# V2_1.net
KiCad netlist of a schematic drawn in Altium Designer
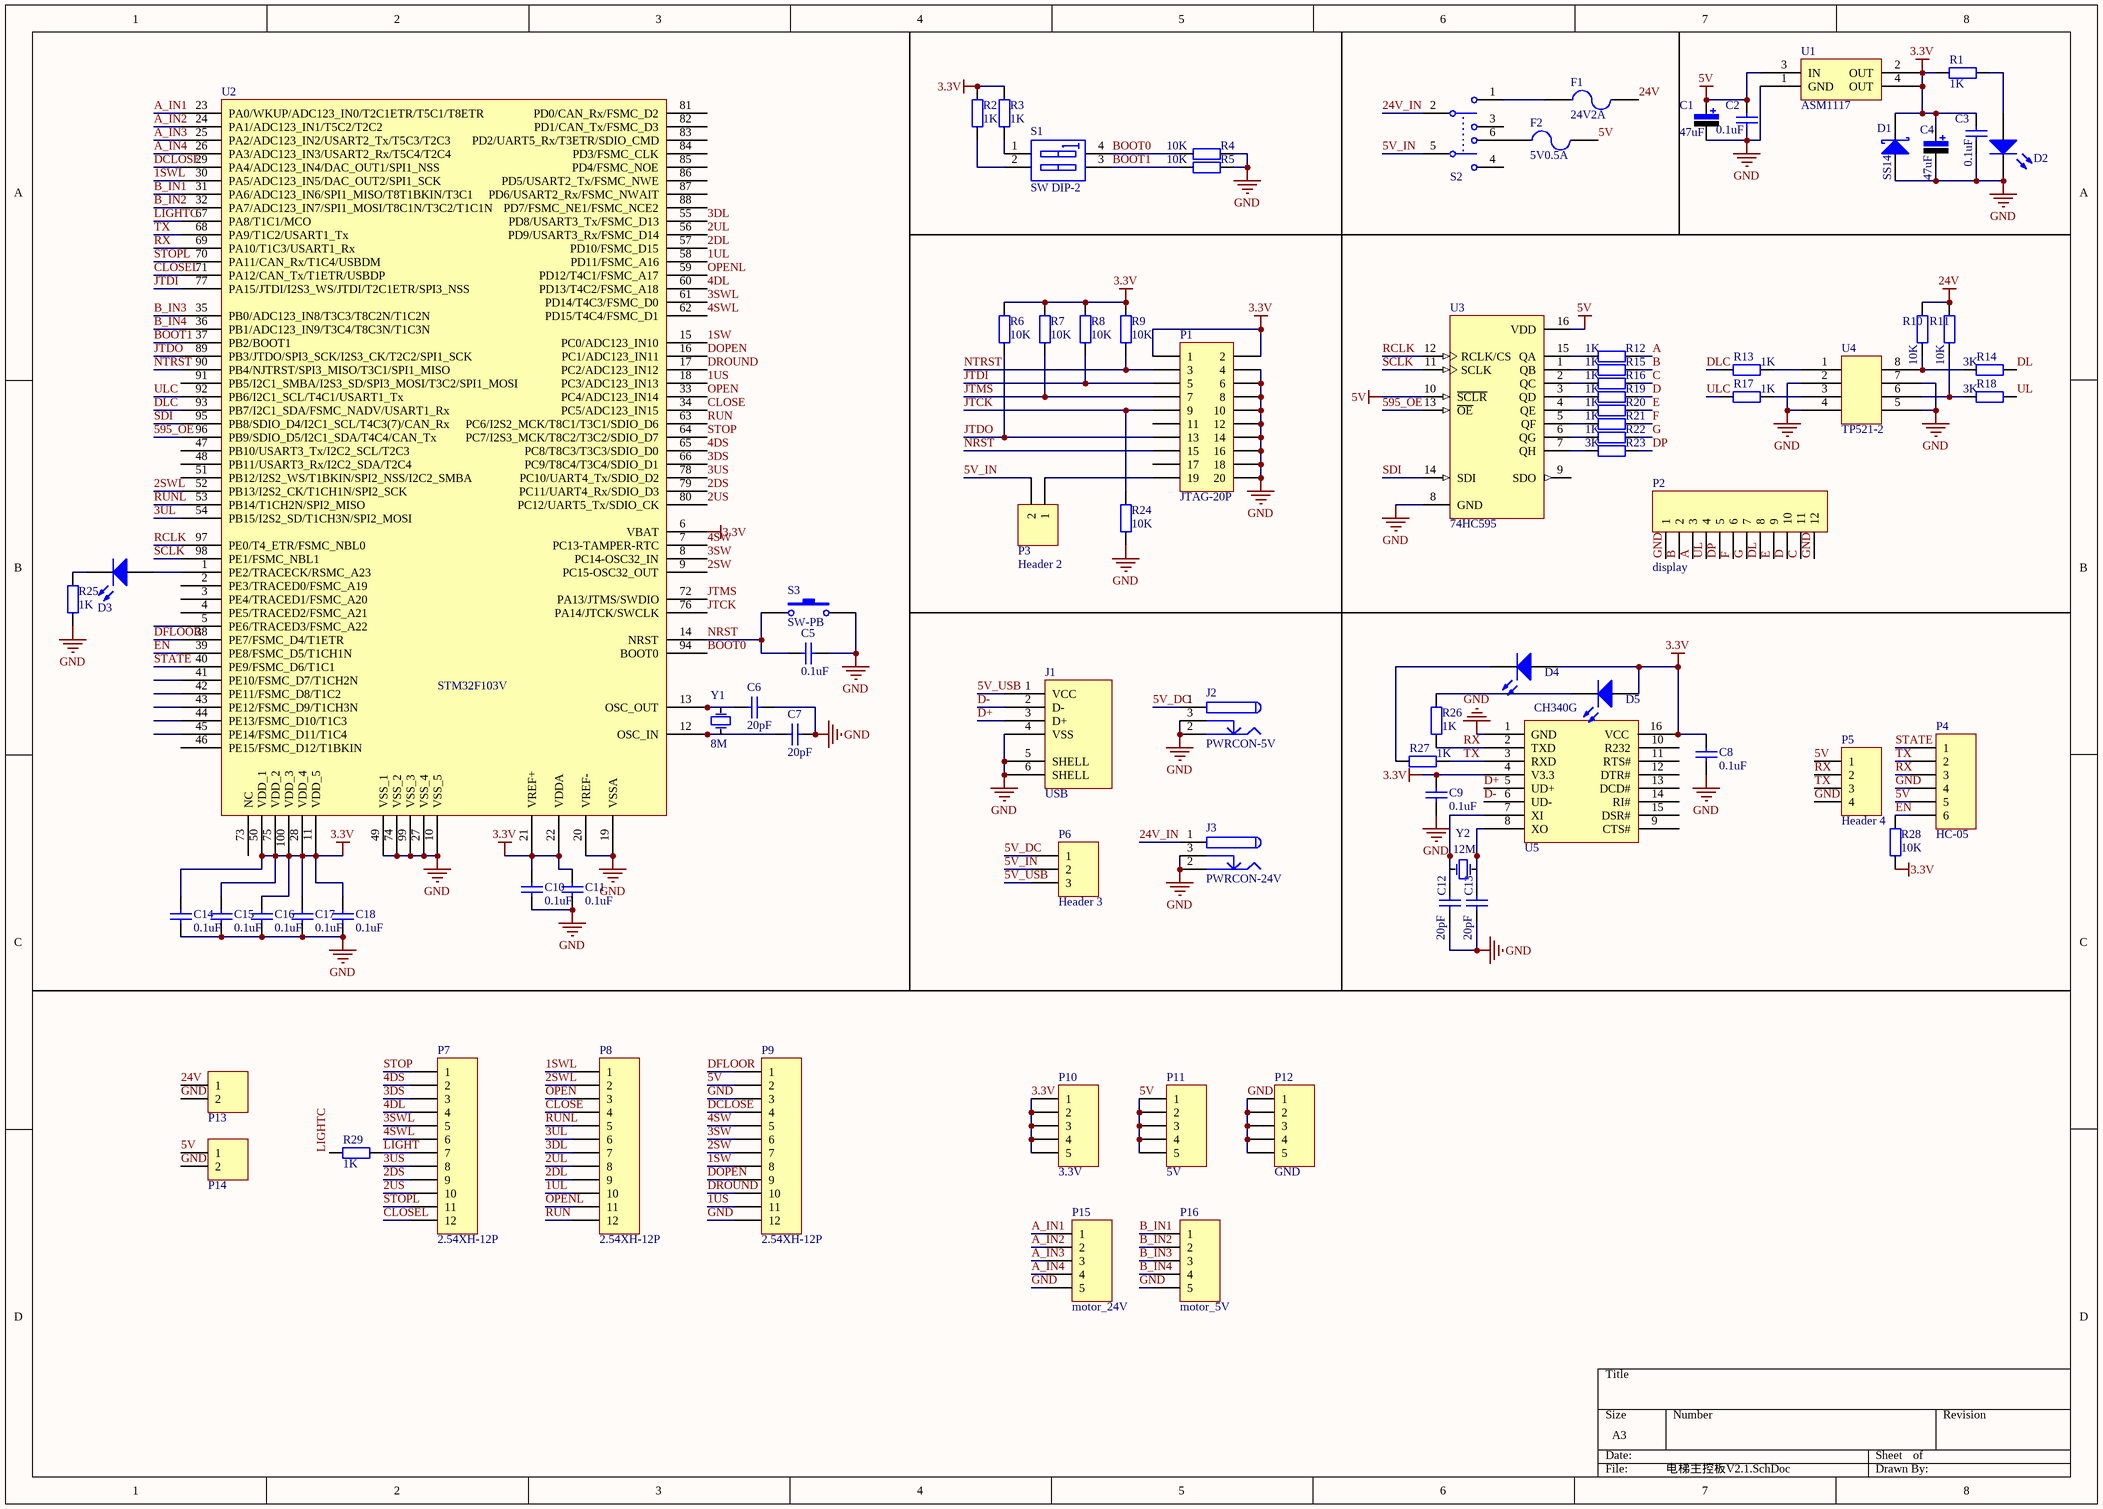
[diagram p0: 电梯主控板V2.1.SchDoc]

(export (version "E")
  (design (tool "Eeschema 10.0.6"))
  (components
    (comp (ref "C1")
      (value "47uF")
      (footprint "CAP-3528")
      (description "钽电容")
      (libsource (lib "Fszhang") (part "Cap-Pol-A"))
    )
    (comp (ref "C2")
      (value "0.1uF")
      (footprint "C-0805")
      (description "贴片瓷片电容")
      (libsource (lib "Fszhang") (part "Cap-S"))
    )
    (comp (ref "C3")
      (value "0.1uF")
      (footprint "C-0805")
      (description "贴片瓷片电容")
      (libsource (lib "Fszhang") (part "Cap-S"))
    )
    (comp (ref "C4")
      (value "47uF")
      (footprint "CAP-3528")
      (description "钽电容")
      (libsource (lib "Fszhang") (part "Cap-Pol-A"))
    )
    (comp (ref "C5")
      (value "0.1uF")
      (footprint "C-0805")
      (description "贴片瓷片电容")
      (libsource (lib "Fszhang") (part "Cap-S"))
    )
    (comp (ref "C6")
      (value "20pF")
      (footprint "C-0805")
      (description "贴片瓷片电容")
      (libsource (lib "Fszhang") (part "Cap-S"))
    )
    (comp (ref "C7")
      (value "20pF")
      (footprint "C-0805")
      (description "贴片瓷片电容")
      (libsource (lib "Fszhang") (part "Cap-S"))
    )
    (comp (ref "C8")
      (value "0.1uF")
      (footprint "C-0805")
      (description "贴片瓷片电容")
      (libsource (lib "Fszhang") (part "Cap-S"))
    )
    (comp (ref "C9")
      (value "0.1uF")
      (footprint "C-0805")
      (description "贴片瓷片电容")
      (libsource (lib "Fszhang") (part "Cap-S"))
    )
    (comp (ref "C10")
      (value "0.1uF")
      (footprint "C-0805")
      (description "贴片瓷片电容")
      (libsource (lib "Fszhang") (part "Cap-S"))
    )
    (comp (ref "C11")
      (value "0.1uF")
      (footprint "C-0805")
      (description "贴片瓷片电容")
      (libsource (lib "Fszhang") (part "Cap-S"))
    )
    (comp (ref "C12")
      (value "20pF")
      (footprint "C-0805")
      (description "贴片瓷片电容")
      (libsource (lib "Fszhang") (part "Cap-S"))
    )
    (comp (ref "C13")
      (value "20pF")
      (footprint "C-0805")
      (description "贴片瓷片电容")
      (libsource (lib "Fszhang") (part "Cap-S"))
    )
    (comp (ref "C14")
      (value "0.1uF")
      (footprint "C-0805")
      (description "贴片瓷片电容")
      (libsource (lib "Fszhang") (part "Cap-S"))
    )
    (comp (ref "C15")
      (value "0.1uF")
      (footprint "C-0805")
      (description "贴片瓷片电容")
      (libsource (lib "Fszhang") (part "Cap-S"))
    )
    (comp (ref "C16")
      (value "0.1uF")
      (footprint "C-0805")
      (description "贴片瓷片电容")
      (libsource (lib "Fszhang") (part "Cap-S"))
    )
    (comp (ref "C17")
      (value "0.1uF")
      (footprint "C-0805")
      (description "贴片瓷片电容")
      (libsource (lib "Fszhang") (part "Cap-S"))
    )
    (comp (ref "C18")
      (value "0.1uF")
      (footprint "C-0805")
      (description "贴片瓷片电容")
      (libsource (lib "Fszhang") (part "Cap-S"))
    )
    (comp (ref "D1")
      (value "Diode-Schottky")
      (footprint "D-SMA")
      (description "肖特基二极管")
      (fields (field (name "TYPE") "SS14"))
      (libsource (lib "Fszhang") (part "Diode-Schottky"))
    )
    (comp (ref "D2")
      (value "LED0")
      (footprint "LED-0805")
      (description "发光二极管")
      (libsource (lib "Fszhang") (part "LED0"))
    )
    (comp (ref "D3")
      (value "LED0")
      (footprint "LED-0805")
      (description "发光二极管")
      (libsource (lib "Fszhang") (part "LED0"))
    )
    (comp (ref "D4")
      (value "LED0")
      (footprint "LED-0805")
      (description "发光二极管")
      (libsource (lib "Fszhang") (part "LED0"))
    )
    (comp (ref "D5")
      (value "LED0")
      (footprint "LED-0805")
      (description "发光二极管")
      (libsource (lib "Fszhang") (part "LED0"))
    )
    (comp (ref "F1")
      (value "24V2A")
      (footprint "1812")
      (description "可恢复保险丝")
      (libsource (lib "Fszhang") (part "Fuse2"))
    )
    (comp (ref "F2")
      (value "5V0.5A")
      (footprint "1812")
      (description "可恢复保险丝")
      (libsource (lib "Fszhang") (part "Fuse2"))
    )
    (comp (ref "J1")
      (value "USB")
      (footprint "USB_A1")
      (description "USB接口")
      (libsource (lib "HDR_Fszhang") (part "USB"))
    )
    (comp (ref "J2")
      (value "PWRCON-5V")
      (footprint "DC-002")
      (description "直流电源端子")
      (libsource (lib "HDR_Fszhang") (part "PWRCON"))
    )
    (comp (ref "J3")
      (value "PWRCON-24V")
      (footprint "DC-005")
      (description "直流电源端子")
      (libsource (lib "HDR_Fszhang") (part "PWRCON"))
    )
    (comp (ref "P1") (value "JTAG-20P") (footprint "DC3-20P") (libsource (lib "natel") (part "JTAG-20P")))
    (comp (ref "P2") (value "display") (footprint "2.54XH-12P") (libsource (lib "natel") (part "2.54XH-12P")))
    (comp (ref "P3")
      (value "Header 2")
      (footprint "HDR1X2")
      (description "Header, 2-Pin")
      (libsource (lib "Miscellaneous Connectors") (part "Header 2"))
    )
    (comp (ref "P4")
      (value "HC-05")
      (footprint "HDR1X6")
      (description "Header, 6-Pin")
      (libsource (lib "Miscellaneous Connectors") (part "Header 6"))
    )
    (comp (ref "P5")
      (value "Header 4")
      (footprint "HDR1X4")
      (description "Header, 4-Pin")
      (libsource (lib "Miscellaneous Connectors") (part "Header 4"))
    )
    (comp (ref "P6")
      (value "Header 3")
      (footprint "HDR1X3")
      (description "Header, 3-Pin")
      (libsource (lib "Miscellaneous Connectors") (part "Header 3"))
    )
    (comp (ref "P7") (value "2.54XH-12P") (footprint "2.54XH-12P") (libsource (lib "") (part "2.54XH-12P_1")))
    (comp (ref "P8") (value "2.54XH-12P") (footprint "2.54XH-12P") (libsource (lib "") (part "2.54XH-12P_1")))
    (comp (ref "P9") (value "2.54XH-12P") (footprint "2.54XH-12P") (libsource (lib "") (part "2.54XH-12P_1")))
    (comp (ref "P10")
      (value "3.3V")
      (footprint "HDR1X5")
      (description "Header, 5-Pin")
      (libsource (lib "Miscellaneous Connectors") (part "Header 5"))
    )
    (comp (ref "P11")
      (value "5V")
      (footprint "HDR1X5")
      (description "Header, 5-Pin")
      (libsource (lib "Miscellaneous Connectors") (part "Header 5"))
    )
    (comp (ref "P12")
      (value "GND")
      (footprint "HDR1X5")
      (description "Header, 5-Pin")
      (libsource (lib "Miscellaneous Connectors") (part "Header 5"))
    )
    (comp (ref "P13") (value "KF301-2P") (footprint "KF301-2P") (libsource (lib "natel") (part "KF301-2P")))
    (comp (ref "P14") (value "KF301-2P") (footprint "KF301-2P") (libsource (lib "natel") (part "KF301-2P")))
    (comp (ref "P15")
      (value "motor_24V")
      (footprint "2.54xh-5P")
      (libsource (lib "natel") (part "2.54XH-5P"))
    )
    (comp (ref "P16") (value "motor_5V") (footprint "2.54xh-5P") (libsource (lib "natel") (part "2.54XH-5P")))
    (comp (ref "R1")
      (value "1K")
      (footprint "0805-1")
      (description "贴片电阻")
      (libsource (lib "Fszhang") (part "Res1"))
    )
    (comp (ref "R2")
      (value "1K")
      (footprint "0805-1")
      (description "贴片电阻")
      (libsource (lib "") (part "Res1_1"))
    )
    (comp (ref "R3")
      (value "1K")
      (footprint "0805-1")
      (description "贴片电阻")
      (libsource (lib "") (part "Res1_1"))
    )
    (comp (ref "R4")
      (value "10K")
      (footprint "0805-1")
      (description "贴片电阻")
      (libsource (lib "Fszhang") (part "Res1"))
    )
    (comp (ref "R5")
      (value "10K")
      (footprint "0805-1")
      (description "贴片电阻")
      (libsource (lib "Fszhang") (part "Res1"))
    )
    (comp (ref "R6")
      (value "10K")
      (footprint "0805-1")
      (description "贴片电阻")
      (libsource (lib "") (part "Res1_1"))
    )
    (comp (ref "R7")
      (value "10K")
      (footprint "0805-1")
      (description "贴片电阻")
      (libsource (lib "") (part "Res1_1"))
    )
    (comp (ref "R8")
      (value "10K")
      (footprint "0805-1")
      (description "贴片电阻")
      (libsource (lib "") (part "Res1_1"))
    )
    (comp (ref "R9")
      (value "10K")
      (footprint "0805-1")
      (description "贴片电阻")
      (libsource (lib "") (part "Res1_1"))
    )
    (comp (ref "R10")
      (value "10K")
      (footprint "0805-1")
      (description "贴片电阻")
      (libsource (lib "") (part "Res1_1"))
    )
    (comp (ref "R11")
      (value "10K")
      (footprint "0805-1")
      (description "贴片电阻")
      (libsource (lib "") (part "Res1_1"))
    )
    (comp (ref "R12")
      (value "1K")
      (footprint "0805-1")
      (description "贴片电阻")
      (libsource (lib "Fszhang") (part "Res1"))
    )
    (comp (ref "R13")
      (value "1K")
      (footprint "0805-1")
      (description "贴片电阻")
      (libsource (lib "Fszhang") (part "Res1"))
    )
    (comp (ref "R14")
      (value "3K")
      (footprint "0805-1")
      (description "贴片电阻")
      (libsource (lib "Fszhang") (part "Res1"))
    )
    (comp (ref "R15")
      (value "1K")
      (footprint "0805-1")
      (description "贴片电阻")
      (libsource (lib "Fszhang") (part "Res1"))
    )
    (comp (ref "R16")
      (value "1K")
      (footprint "0805-1")
      (description "贴片电阻")
      (libsource (lib "Fszhang") (part "Res1"))
    )
    (comp (ref "R17")
      (value "1K")
      (footprint "0805-1")
      (description "贴片电阻")
      (libsource (lib "Fszhang") (part "Res1"))
    )
    (comp (ref "R18")
      (value "3K")
      (footprint "0805-1")
      (description "贴片电阻")
      (libsource (lib "Fszhang") (part "Res1"))
    )
    (comp (ref "R19")
      (value "1K")
      (footprint "0805-1")
      (description "贴片电阻")
      (libsource (lib "Fszhang") (part "Res1"))
    )
    (comp (ref "R20")
      (value "1K")
      (footprint "0805-1")
      (description "贴片电阻")
      (libsource (lib "Fszhang") (part "Res1"))
    )
    (comp (ref "R21")
      (value "1K")
      (footprint "0805-1")
      (description "贴片电阻")
      (libsource (lib "Fszhang") (part "Res1"))
    )
    (comp (ref "R22")
      (value "1K")
      (footprint "0805-1")
      (description "贴片电阻")
      (libsource (lib "Fszhang") (part "Res1"))
    )
    (comp (ref "R23")
      (value "3K")
      (footprint "0805-1")
      (description "贴片电阻")
      (libsource (lib "Fszhang") (part "Res1"))
    )
    (comp (ref "R24")
      (value "10K")
      (footprint "0805-1")
      (description "贴片电阻")
      (libsource (lib "") (part "Res1_1"))
    )
    (comp (ref "R25")
      (value "1K")
      (footprint "0805-1")
      (description "贴片电阻")
      (libsource (lib "") (part "Res1_1"))
    )
    (comp (ref "R26")
      (value "1K")
      (footprint "0805-1")
      (description "贴片电阻")
      (libsource (lib "") (part "Res1_1"))
    )
    (comp (ref "R27")
      (value "1K")
      (footprint "0805-1")
      (description "贴片电阻")
      (libsource (lib "Fszhang") (part "Res1"))
    )
    (comp (ref "R28")
      (value "10K")
      (footprint "0805-1")
      (description "贴片电阻")
      (libsource (lib "") (part "Res1_1"))
    )
    (comp (ref "R29")
      (value "1K")
      (footprint "0805-1")
      (description "贴片电阻")
      (libsource (lib "Fszhang") (part "Res1"))
    )
    (comp (ref "S1")
      (value "SW DIP-2")
      (footprint "DIP-4")
      (description "DIP Switch, 2 Position, SPST")
      (libsource (lib "Miscellaneous Devices") (part "SW DIP-2"))
    )
    (comp (ref "S2") (value "六脚钮子开关") (footprint "六脚纽子开关") (libsource (lib "natel") (part "六脚钮子开关")))
    (comp (ref "S3")
      (value "SW-PB")
      (footprint "SW_PB2_A1")
      (description "微动开关")
      (libsource (lib "Fszhang") (part "SW-PB"))
    )
    (comp (ref "U1")
      (value "ASM1117")
      (footprint "SOT223")
      (description "3.3V稳压芯片")
      (libsource (lib "Fszhang") (part "ASM1117"))
    )
    (comp (ref "U2")
      (value "STM32F103V")
      (footprint "LQFP-100")
      (description "STM32单片机100引脚")
      (libsource (lib "Fszhang") (part "STM32F103V"))
    )
    (comp (ref "U3")
      (value "74HC595")
      (footprint "SOIC-16")
      (description "移位寄存器")
      (libsource (lib "Fszhang") (part "74HC595"))
    )
    (comp (ref "U4") (value "TP521-2") (footprint "DIP8") (libsource (lib "natel") (part "P521-2")))
    (comp (ref "U5") (value "CH340G") (footprint "SOP16") (libsource (lib "natel") (part "CH340G")))
    (comp (ref "Y1")
      (value "8M")
      (footprint "X-HC-49S")
      (description "晶振")
      (libsource (lib "Fszhang") (part "XTAL"))
    )
    (comp (ref "Y2")
      (value "12M")
      (footprint "X-HC-49S")
      (description "晶振")
      (libsource (lib "Fszhang") (part "XTAL"))
    )
  )
  (nets
    (net (code "1") (name "/1SW") (class "Default")
      (node (ref "P9") (pin "8") (pinfunction "8_8") (pintype "passive"))
      (node (ref "U2") (pin "15") (pinfunction "PC0/ADC123_IN10_15") (pintype "passive"))
    )
    (net (code "2") (name "/1SWL") (class "Default")
      (node (ref "P8") (pin "1") (pinfunction "1_1") (pintype "passive"))
      (node (ref "U2") (pin "30") (pinfunction "PA5/ADC123_IN5/DAC_OUT2/SPI1_SCK_30") (pintype "passive"))
    )
    (net (code "3") (name "/1UL") (class "Default")
      (node (ref "P8") (pin "10") (pinfunction "10_10") (pintype "passive"))
      (node (ref "U2") (pin "58") (pinfunction "PD11/FSMC_A16_58") (pintype "passive"))
    )
    (net (code "4") (name "/1US") (class "Default")
      (node (ref "P9") (pin "11") (pinfunction "11_11") (pintype "passive"))
      (node (ref "U2") (pin "18") (pinfunction "PC3/ADC123_IN13_18") (pintype "passive"))
    )
    (net (code "5") (name "/2DL") (class "Default")
      (node (ref "P8") (pin "9") (pinfunction "9_9") (pintype "passive"))
      (node (ref "U2") (pin "57") (pinfunction "PD10/FSMC_D15_57") (pintype "passive"))
    )
    (net (code "6") (name "/2DS") (class "Default")
      (node (ref "P7") (pin "9") (pinfunction "9_9") (pintype "passive"))
      (node (ref "U2") (pin "79") (pinfunction "PC11/UART4_Rx/SDIO_D3_79") (pintype "passive"))
    )
    (net (code "7") (name "/2SW") (class "Default")
      (node (ref "P9") (pin "7") (pinfunction "7_7") (pintype "passive"))
      (node (ref "U2") (pin "9") (pinfunction "PC15-OSC32_OUT_9") (pintype "passive"))
    )
    (net (code "8") (name "/2SWL") (class "Default")
      (node (ref "P8") (pin "2") (pinfunction "2_2") (pintype "passive"))
      (node (ref "U2") (pin "52") (pinfunction "PB13/I2S2_CK/T1CH1N/SPI2_SCK_52") (pintype "passive"))
    )
    (net (code "9") (name "/2UL") (class "Default")
      (node (ref "P8") (pin "8") (pinfunction "8_8") (pintype "passive"))
      (node (ref "U2") (pin "56") (pinfunction "PD9/USART3_Rx/FSMC_D14_56") (pintype "passive"))
    )
    (net (code "10") (name "/2US") (class "Default")
      (node (ref "P7") (pin "10") (pinfunction "10_10") (pintype "passive"))
      (node (ref "U2") (pin "80") (pinfunction "PC12/UART5_Tx/SDIO_CK_80") (pintype "passive"))
    )
    (net (code "11") (name "/3DL") (class "Default")
      (node (ref "P8") (pin "7") (pinfunction "7_7") (pintype "passive"))
      (node (ref "U2") (pin "55") (pinfunction "PD8/USART3_Tx/FSMC_D13_55") (pintype "passive"))
    )
    (net (code "12") (name "/3DS") (class "Default")
      (node (ref "P7") (pin "3") (pinfunction "3_3") (pintype "passive"))
      (node (ref "U2") (pin "66") (pinfunction "PC9/T8C4/T3C4/SDIO_D1_66") (pintype "passive"))
    )
    (net (code "13") (name "/3SW") (class "Default")
      (node (ref "P9") (pin "6") (pinfunction "6_6") (pintype "passive"))
      (node (ref "U2") (pin "8") (pinfunction "PC14-OSC32_IN_8") (pintype "passive"))
    )
    (net (code "14") (name "/3SWL") (class "Default")
      (node (ref "P7") (pin "5") (pinfunction "5_5") (pintype "passive"))
      (node (ref "U2") (pin "61") (pinfunction "PD14/T4C3/FSMC_D0_61") (pintype "passive"))
    )
    (net (code "15") (name "/3UL") (class "Default")
      (node (ref "P8") (pin "6") (pinfunction "6_6") (pintype "passive"))
      (node (ref "U2") (pin "54") (pinfunction "PB15/I2S2_SD/T1CH3N/SPI2_MOSI_54") (pintype "passive"))
    )
    (net (code "16") (name "/3US") (class "Default")
      (node (ref "P7") (pin "8") (pinfunction "8_8") (pintype "passive"))
      (node (ref "U2") (pin "78") (pinfunction "PC10/UART4_Tx/SDIO_D2_78") (pintype "passive"))
    )
    (net (code "17") (name "/4DL") (class "Default")
      (node (ref "P7") (pin "4") (pinfunction "4_4") (pintype "passive"))
      (node (ref "U2") (pin "60") (pinfunction "PD13/T4C2/FSMC_A18_60") (pintype "passive"))
    )
    (net (code "18") (name "/4DS") (class "Default")
      (node (ref "P7") (pin "2") (pinfunction "2_2") (pintype "passive"))
      (node (ref "U2") (pin "65") (pinfunction "PC8/T8C3/T3C3/SDIO_D0_65") (pintype "passive"))
    )
    (net (code "19") (name "/4SW") (class "Default")
      (node (ref "P9") (pin "5") (pinfunction "5_5") (pintype "passive"))
      (node (ref "U2") (pin "7") (pinfunction "PC13-TAMPER-RTC_7") (pintype "passive"))
    )
    (net (code "20") (name "/4SWL") (class "Default")
      (node (ref "P7") (pin "6") (pinfunction "6_6") (pintype "passive"))
      (node (ref "U2") (pin "62") (pinfunction "PD15/T4C4/FSMC_D1_62") (pintype "passive"))
    )
    (net (code "21") (name "/5V_DC") (class "Default")
      (node (ref "J2") (pin "1") (pinfunction "1_1") (pintype "power_in"))
      (node (ref "P6") (pin "1") (pinfunction "1_1") (pintype "passive"))
    )
    (net (code "22") (name "/5V_IN") (class "Default")
      (node (ref "P3") (pin "2") (pinfunction "2_2") (pintype "passive"))
      (node (ref "P6") (pin "2") (pinfunction "2_2") (pintype "passive"))
      (node (ref "S2") (pin "5") (pinfunction "5_5") (pintype "passive"))
    )
    (net (code "23") (name "/5V_USB") (class "Default")
      (node (ref "J1") (pin "1") (pinfunction "VCC_1") (pintype "passive"))
      (node (ref "P6") (pin "3") (pinfunction "3_3") (pintype "passive"))
    )
    (net (code "24") (name "/24V_IN") (class "Default")
      (node (ref "J3") (pin "1") (pinfunction "1_1") (pintype "power_in"))
      (node (ref "S2") (pin "2") (pinfunction "2_2") (pintype "passive"))
    )
    (net (code "25") (name "/595_OE") (class "Default")
      (node (ref "U2") (pin "96") (pinfunction "PB9/SDIO_D5/I2C1_SDA/T4C4/CAN_Tx_96") (pintype "passive"))
      (node (ref "U3") (pin "13") (pinfunction "~{OE}_13") (pintype "input"))
    )
    (net (code "26") (name "/A") (class "Default")
      (node (ref "P2") (pin "3") (pinfunction "3_3") (pintype "passive"))
      (node (ref "R12") (pin "2") (pinfunction "2_2") (pintype "passive"))
    )
    (net (code "27") (name "/A_IN1") (class "Default")
      (node (ref "P15") (pin "1") (pinfunction "1_1") (pintype "passive"))
      (node (ref "U2") (pin "23") (pinfunction "PA0/WKUP/ADC123_IN0/T2C1ETR/T5C1/T8ETR_23") (pintype "passive"))
    )
    (net (code "28") (name "/A_IN2") (class "Default")
      (node (ref "P15") (pin "2") (pinfunction "2_2") (pintype "passive"))
      (node (ref "U2") (pin "24") (pinfunction "PA1/ADC123_IN1/T5C2/T2C2_24") (pintype "passive"))
    )
    (net (code "29") (name "/A_IN3") (class "Default")
      (node (ref "P15") (pin "3") (pinfunction "3_3") (pintype "passive"))
      (node (ref "U2") (pin "25") (pinfunction "PA2/ADC123_IN2/USART2_Tx/T5C3/T2C3_25") (pintype "passive"))
    )
    (net (code "30") (name "/A_IN4") (class "Default")
      (node (ref "P15") (pin "4") (pinfunction "4_4") (pintype "passive"))
      (node (ref "U2") (pin "26") (pinfunction "PA3/ADC123_IN3/USART2_Rx/T5C4/T2C4_26") (pintype "passive"))
    )
    (net (code "31") (name "/B") (class "Default")
      (node (ref "P2") (pin "2") (pinfunction "2_2") (pintype "passive"))
      (node (ref "R15") (pin "2") (pinfunction "2_2") (pintype "passive"))
    )
    (net (code "32") (name "/BOOT0") (class "Default")
      (node (ref "R4") (pin "1") (pinfunction "1_1") (pintype "passive"))
      (node (ref "S1") (pin "4") (pinfunction "B1_4") (pintype "passive"))
      (node (ref "U2") (pin "94") (pinfunction "BOOT0_94") (pintype "passive"))
    )
    (net (code "33") (name "/BOOT1") (class "Default")
      (node (ref "R5") (pin "1") (pinfunction "1_1") (pintype "passive"))
      (node (ref "S1") (pin "3") (pinfunction "B2_3") (pintype "passive"))
      (node (ref "U2") (pin "37") (pinfunction "PB2/BOOT1_37") (pintype "passive"))
    )
    (net (code "34") (name "/B_IN1") (class "Default")
      (node (ref "P16") (pin "1") (pinfunction "1_1") (pintype "passive"))
      (node (ref "U2") (pin "31") (pinfunction "PA6/ADC123_IN6/SPI1_MISO/T8T1BKIN/T3C1_31") (pintype "passive"))
    )
    (net (code "35") (name "/B_IN2") (class "Default")
      (node (ref "P16") (pin "2") (pinfunction "2_2") (pintype "passive"))
      (node (ref "U2") (pin "32") (pinfunction "PA7/ADC123_IN7/SPI1_MOSI/T8C1N/T3C2/T1C1N_32") (pintype "passive"))
    )
    (net (code "36") (name "/B_IN3") (class "Default")
      (node (ref "P16") (pin "3") (pinfunction "3_3") (pintype "passive"))
      (node (ref "U2") (pin "35") (pinfunction "PB0/ADC123_IN8/T3C3/T8C2N/T1C2N_35") (pintype "passive"))
    )
    (net (code "37") (name "/B_IN4") (class "Default")
      (node (ref "P16") (pin "4") (pinfunction "4_4") (pintype "passive"))
      (node (ref "U2") (pin "36") (pinfunction "PB1/ADC123_IN9/T3C4/T8C3N/T1C3N_36") (pintype "passive"))
    )
    (net (code "38") (name "/C") (class "Default")
      (node (ref "P2") (pin "11") (pinfunction "11_11") (pintype "passive"))
      (node (ref "R16") (pin "2") (pinfunction "2_2") (pintype "passive"))
    )
    (net (code "39") (name "/CLOSE") (class "Default")
      (node (ref "P8") (pin "4") (pinfunction "4_4") (pintype "passive"))
      (node (ref "U2") (pin "34") (pinfunction "PC5/ADC123_IN15_34") (pintype "passive"))
    )
    (net (code "40") (name "/CLOSEL") (class "Default")
      (node (ref "P7") (pin "12") (pinfunction "12_12") (pintype "passive"))
      (node (ref "U2") (pin "71") (pinfunction "PA12/CAN_Tx/T1ETR/USBDP_71") (pintype "passive"))
    )
    (net (code "41") (name "/D") (class "Default")
      (node (ref "P2") (pin "10") (pinfunction "10_10") (pintype "passive"))
      (node (ref "R19") (pin "2") (pinfunction "2_2") (pintype "passive"))
    )
    (net (code "42") (name "/D+") (class "Default")
      (node (ref "J1") (pin "3") (pinfunction "D+_3") (pintype "passive"))
      (node (ref "U5") (pin "5") (pinfunction "UD+_5") (pintype "passive"))
    )
    (net (code "43") (name "/D-") (class "Default")
      (node (ref "J1") (pin "2") (pinfunction "D-_2") (pintype "passive"))
      (node (ref "U5") (pin "6") (pinfunction "UD-_6") (pintype "passive"))
    )
    (net (code "44") (name "/DCLOSE") (class "Default")
      (node (ref "P9") (pin "4") (pinfunction "4_4") (pintype "passive"))
      (node (ref "U2") (pin "29") (pinfunction "PA4/ADC123_IN4/DAC_OUT1/SPI1_NSS_29") (pintype "passive"))
    )
    (net (code "45") (name "/DFLOOR") (class "Default")
      (node (ref "P9") (pin "1") (pinfunction "1_1") (pintype "passive"))
      (node (ref "U2") (pin "38") (pinfunction "PE7/FSMC_D4/T1ETR_38") (pintype "passive"))
    )
    (net (code "46") (name "/DL") (class "Default")
      (node (ref "P2") (pin "8") (pinfunction "8_8") (pintype "passive"))
      (node (ref "R14") (pin "2") (pinfunction "2_2") (pintype "passive"))
    )
    (net (code "47") (name "/DLC") (class "Default")
      (node (ref "R13") (pin "1") (pinfunction "1_1") (pintype "passive"))
      (node (ref "U2") (pin "93") (pinfunction "PB7/I2C1_SDA/FSMC_NADV/USART1_Rx_93") (pintype "passive"))
    )
    (net (code "48") (name "/DOPEN") (class "Default")
      (node (ref "P9") (pin "9") (pinfunction "9_9") (pintype "passive"))
      (node (ref "U2") (pin "16") (pinfunction "PC1/ADC123_IN11_16") (pintype "passive"))
    )
    (net (code "49") (name "/DP") (class "Default")
      (node (ref "P2") (pin "5") (pinfunction "5_5") (pintype "passive"))
      (node (ref "R23") (pin "2") (pinfunction "2_2") (pintype "passive"))
    )
    (net (code "50") (name "/DROUND") (class "Default")
      (node (ref "P9") (pin "10") (pinfunction "10_10") (pintype "passive"))
      (node (ref "U2") (pin "17") (pinfunction "PC2/ADC123_IN12_17") (pintype "passive"))
    )
    (net (code "51") (name "/E") (class "Default")
      (node (ref "P2") (pin "9") (pinfunction "9_9") (pintype "passive"))
      (node (ref "R20") (pin "2") (pinfunction "2_2") (pintype "passive"))
    )
    (net (code "52") (name "/EN") (class "Default")
      (node (ref "P4") (pin "6") (pinfunction "6_6") (pintype "passive"))
      (node (ref "R28") (pin "2") (pinfunction "2_2") (pintype "passive"))
      (node (ref "U2") (pin "39") (pinfunction "PE8/FSMC_D5/T1CH1N_39") (pintype "passive"))
    )
    (net (code "53") (name "/F") (class "Default")
      (node (ref "P2") (pin "6") (pinfunction "6_6") (pintype "passive"))
      (node (ref "R21") (pin "2") (pinfunction "2_2") (pintype "passive"))
    )
    (net (code "54") (name "/G") (class "Default")
      (node (ref "P2") (pin "7") (pinfunction "7_7") (pintype "passive"))
      (node (ref "R22") (pin "2") (pinfunction "2_2") (pintype "passive"))
    )
    (net (code "55") (name "/JTCK") (class "Default")
      (node (ref "P1") (pin "9") (pinfunction "9_9") (pintype "passive"))
      (node (ref "R24") (pin "2") (pinfunction "2_2") (pintype "passive"))
      (node (ref "U2") (pin "76") (pinfunction "PA14/JTCK/SWCLK_76") (pintype "passive"))
    )
    (net (code "56") (name "/JTDI") (class "Default")
      (node (ref "P1") (pin "5") (pinfunction "5_5") (pintype "passive"))
      (node (ref "R8") (pin "1") (pinfunction "1_1") (pintype "passive"))
      (node (ref "U2") (pin "77") (pinfunction "PA15/JTDI/I2S3_WS/JTDI/T2C1ETR/SPI3_NSS_77") (pintype "passive"))
    )
    (net (code "57") (name "/JTDO") (class "Default")
      (node (ref "P1") (pin "13") (pinfunction "13_13") (pintype "passive"))
      (node (ref "R6") (pin "1") (pinfunction "1_1") (pintype "passive"))
      (node (ref "U2") (pin "89") (pinfunction "PB3/JTDO/SPI3_SCK/I2S3_CK/T2C2/SPI1_SCK_89") (pintype "passive"))
    )
    (net (code "58") (name "/JTMS") (class "Default")
      (node (ref "P1") (pin "7") (pinfunction "7_7") (pintype "passive"))
      (node (ref "R7") (pin "1") (pinfunction "1_1") (pintype "passive"))
      (node (ref "U2") (pin "72") (pinfunction "PA13/JTMS/SWDIO_72") (pintype "passive"))
    )
    (net (code "59") (name "/LIGHT") (class "Default")
      (node (ref "P7") (pin "7") (pinfunction "7_7") (pintype "passive"))
      (node (ref "R29") (pin "2") (pinfunction "2_2") (pintype "passive"))
    )
    (net (code "60") (name "/LIGHTC") (class "Default")
      (node (ref "R29") (pin "1") (pinfunction "1_1") (pintype "passive"))
      (node (ref "U2") (pin "67") (pinfunction "PA8/T1C1/MCO_67") (pintype "passive"))
    )
    (net (code "61") (name "/NRST") (class "Default")
      (node (ref "C5") (pin "1") (pinfunction "1_1") (pintype "passive"))
      (node (ref "P1") (pin "15") (pinfunction "15_15") (pintype "passive"))
      (node (ref "S3") (pin "1") (pinfunction "1_1") (pintype "passive"))
      (node (ref "U2") (pin "14") (pinfunction "NRST_14") (pintype "passive"))
    )
    (net (code "62") (name "/NTRST") (class "Default")
      (node (ref "P1") (pin "3") (pinfunction "3_3") (pintype "passive"))
      (node (ref "R9") (pin "1") (pinfunction "1_1") (pintype "passive"))
      (node (ref "U2") (pin "90") (pinfunction "PB4/NJTRST/SPI3_MISO/T3C1/SPI1_MISO_90") (pintype "passive"))
    )
    (net (code "63") (name "/OPEN") (class "Default")
      (node (ref "P8") (pin "3") (pinfunction "3_3") (pintype "passive"))
      (node (ref "U2") (pin "33") (pinfunction "PC4/ADC123_IN14_33") (pintype "passive"))
    )
    (net (code "64") (name "/OPENL") (class "Default")
      (node (ref "P8") (pin "11") (pinfunction "11_11") (pintype "passive"))
      (node (ref "U2") (pin "59") (pinfunction "PD12/T4C1/FSMC_A17_59") (pintype "passive"))
    )
    (net (code "65") (name "/RCLK") (class "Default")
      (node (ref "U2") (pin "97") (pinfunction "PE0/T4_ETR/FSMC_NBL0_97") (pintype "passive"))
      (node (ref "U3") (pin "12") (pinfunction "RCLK/CS_12") (pintype "input"))
    )
    (net (code "66") (name "/RUN") (class "Default")
      (node (ref "P8") (pin "12") (pinfunction "12_12") (pintype "passive"))
      (node (ref "U2") (pin "63") (pinfunction "PC6/I2S2_MCK/T8C1/T3C1/SDIO_D6_63") (pintype "passive"))
    )
    (net (code "67") (name "/RUNL") (class "Default")
      (node (ref "P8") (pin "5") (pinfunction "5_5") (pintype "passive"))
      (node (ref "U2") (pin "53") (pinfunction "PB14/T1CH2N/SPI2_MISO_53") (pintype "passive"))
    )
    (net (code "68") (name "/RX") (class "Default")
      (node (ref "P4") (pin "3") (pinfunction "3_3") (pintype "passive"))
      (node (ref "P5") (pin "2") (pinfunction "2_2") (pintype "passive"))
      (node (ref "R26") (pin "1") (pinfunction "1_1") (pintype "passive"))
      (node (ref "U2") (pin "69") (pinfunction "PA10/T1C3/USART1_Rx_69") (pintype "passive"))
      (node (ref "U5") (pin "2") (pinfunction "TXD_2") (pintype "passive"))
    )
    (net (code "69") (name "/SCLK") (class "Default")
      (node (ref "U2") (pin "98") (pinfunction "PE1/FSMC_NBL1_98") (pintype "passive"))
      (node (ref "U3") (pin "11") (pinfunction "SCLK_11") (pintype "input"))
    )
    (net (code "70") (name "/SDI") (class "Default")
      (node (ref "U2") (pin "95") (pinfunction "PB8/SDIO_D4/I2C1_SCL/T4C3(7)/CAN_Rx_95") (pintype "passive"))
      (node (ref "U3") (pin "14") (pinfunction "SDI_14") (pintype "input"))
    )
    (net (code "71") (name "/STATE") (class "Default")
      (node (ref "P4") (pin "1") (pinfunction "1_1") (pintype "passive"))
      (node (ref "U2") (pin "40") (pinfunction "PE9/FSMC_D6/T1C1_40") (pintype "passive"))
    )
    (net (code "72") (name "/STOP") (class "Default")
      (node (ref "P7") (pin "1") (pinfunction "1_1") (pintype "passive"))
      (node (ref "U2") (pin "64") (pinfunction "PC7/I2S3_MCK/T8C2/T3C2/SDIO_D7_64") (pintype "passive"))
    )
    (net (code "73") (name "/STOPL") (class "Default")
      (node (ref "P7") (pin "11") (pinfunction "11_11") (pintype "passive"))
      (node (ref "U2") (pin "70") (pinfunction "PA11/CAN_Rx/T1C4/USBDM_70") (pintype "passive"))
    )
    (net (code "74") (name "/TX") (class "Default")
      (node (ref "P4") (pin "2") (pinfunction "2_2") (pintype "passive"))
      (node (ref "P5") (pin "3") (pinfunction "3_3") (pintype "passive"))
      (node (ref "R27") (pin "2") (pinfunction "2_2") (pintype "passive"))
      (node (ref "U2") (pin "68") (pinfunction "PA9/T1C2/USART1_Tx_68") (pintype "passive"))
      (node (ref "U5") (pin "3") (pinfunction "RXD_3") (pintype "passive"))
    )
    (net (code "75") (name "/UL") (class "Default")
      (node (ref "P2") (pin "4") (pinfunction "4_4") (pintype "passive"))
      (node (ref "R18") (pin "2") (pinfunction "2_2") (pintype "passive"))
    )
    (net (code "76") (name "/ULC") (class "Default")
      (node (ref "R17") (pin "1") (pinfunction "1_1") (pintype "passive"))
      (node (ref "U2") (pin "92") (pinfunction "PB6/I2C1_SCL/T4C1/USART1_Tx_92") (pintype "passive"))
    )
    (net (code "77") (name "3.3V") (class "Default")
      (node (ref "C10") (pin "2") (pinfunction "2_2") (pintype "passive"))
      (node (ref "C11") (pin "2") (pinfunction "2_2") (pintype "passive"))
      (node (ref "C14") (pin "2") (pinfunction "2_2") (pintype "passive"))
      (node (ref "C15") (pin "2") (pinfunction "2_2") (pintype "passive"))
      (node (ref "C16") (pin "2") (pinfunction "2_2") (pintype "passive"))
      (node (ref "C17") (pin "2") (pinfunction "2_2") (pintype "passive"))
      (node (ref "C18") (pin "2") (pinfunction "2_2") (pintype "passive"))
      (node (ref "C3") (pin "2") (pinfunction "2_2") (pintype "passive"))
      (node (ref "C4") (pin "1") (pinfunction "1_1") (pintype "passive"))
      (node (ref "C8") (pin "2") (pinfunction "2_2") (pintype "passive"))
      (node (ref "C9") (pin "2") (pinfunction "2_2") (pintype "passive"))
      (node (ref "D1") (pin "2") (pinfunction "K_2") (pintype "passive"))
      (node (ref "D4") (pin "1") (pinfunction "A_1") (pintype "passive"))
      (node (ref "D5") (pin "1") (pinfunction "A_1") (pintype "passive"))
      (node (ref "P1") (pin "1") (pinfunction "1_1") (pintype "passive"))
      (node (ref "P1") (pin "2") (pinfunction "2_2") (pintype "passive"))
      (node (ref "P10") (pin "1") (pinfunction "1_1") (pintype "passive"))
      (node (ref "P10") (pin "2") (pinfunction "2_2") (pintype "passive"))
      (node (ref "P10") (pin "3") (pinfunction "3_3") (pintype "passive"))
      (node (ref "P10") (pin "4") (pinfunction "4_4") (pintype "passive"))
      (node (ref "P10") (pin "5") (pinfunction "5_5") (pintype "passive"))
      (node (ref "R1") (pin "1") (pinfunction "1_1") (pintype "passive"))
      (node (ref "R2") (pin "2") (pinfunction "2_2") (pintype "passive"))
      (node (ref "R28") (pin "1") (pinfunction "1_1") (pintype "passive"))
      (node (ref "R3") (pin "2") (pinfunction "2_2") (pintype "passive"))
      (node (ref "R6") (pin "2") (pinfunction "2_2") (pintype "passive"))
      (node (ref "R7") (pin "2") (pinfunction "2_2") (pintype "passive"))
      (node (ref "R8") (pin "2") (pinfunction "2_2") (pintype "passive"))
      (node (ref "R9") (pin "2") (pinfunction "2_2") (pintype "passive"))
      (node (ref "U1") (pin "2") (pinfunction "OUT_2") (pintype "passive"))
      (node (ref "U1") (pin "4") (pinfunction "OUT_4") (pintype "passive"))
      (node (ref "U2") (pin "100") (pinfunction "VDD_3_100") (pintype "passive"))
      (node (ref "U2") (pin "11") (pinfunction "VDD_5_11") (pintype "passive"))
      (node (ref "U2") (pin "21") (pinfunction "VREF+_21") (pintype "passive"))
      (node (ref "U2") (pin "22") (pinfunction "VDDA_22") (pintype "passive"))
      (node (ref "U2") (pin "28") (pinfunction "VDD_4_28") (pintype "passive"))
      (node (ref "U2") (pin "50") (pinfunction "VDD_1_50") (pintype "passive"))
      (node (ref "U2") (pin "6") (pinfunction "VBAT_6") (pintype "passive"))
      (node (ref "U2") (pin "75") (pinfunction "VDD_2_75") (pintype "passive"))
      (node (ref "U5") (pin "16") (pinfunction "VCC_16") (pintype "passive"))
      (node (ref "U5") (pin "4") (pinfunction "V3.3_4") (pintype "passive"))
    )
    (net (code "78") (name "5V") (class "Default")
      (node (ref "C1") (pin "1") (pinfunction "1_1") (pintype "passive"))
      (node (ref "C2") (pin "2") (pinfunction "2_2") (pintype "passive"))
      (node (ref "F2") (pin "2") (pinfunction "2_2") (pintype "passive"))
      (node (ref "P11") (pin "1") (pinfunction "1_1") (pintype "passive"))
      (node (ref "P11") (pin "2") (pinfunction "2_2") (pintype "passive"))
      (node (ref "P11") (pin "3") (pinfunction "3_3") (pintype "passive"))
      (node (ref "P11") (pin "4") (pinfunction "4_4") (pintype "passive"))
      (node (ref "P11") (pin "5") (pinfunction "5_5") (pintype "passive"))
      (node (ref "P14") (pin "1") (pinfunction "1_1") (pintype "passive"))
      (node (ref "P4") (pin "5") (pinfunction "5_5") (pintype "passive"))
      (node (ref "P5") (pin "1") (pinfunction "1_1") (pintype "passive"))
      (node (ref "P9") (pin "2") (pinfunction "2_2") (pintype "passive"))
      (node (ref "U1") (pin "3") (pinfunction "IN_3") (pintype "passive"))
      (node (ref "U3") (pin "10") (pinfunction "~{SCLR}_10") (pintype "input"))
      (node (ref "U3") (pin "16") (pinfunction "VDD_16") (pintype "power_in"))
    )
    (net (code "79") (name "24V") (class "Default")
      (node (ref "F1") (pin "2") (pinfunction "2_2") (pintype "passive"))
      (node (ref "P13") (pin "1") (pinfunction "1_1") (pintype "passive"))
      (node (ref "R10") (pin "2") (pinfunction "2_2") (pintype "passive"))
      (node (ref "R11") (pin "2") (pinfunction "2_2") (pintype "passive"))
    )
    (net (code "80") (name "GND") (class "Default")
      (node (ref "C1") (pin "2") (pinfunction "2_2") (pintype "passive"))
      (node (ref "C10") (pin "1") (pinfunction "1_1") (pintype "passive"))
      (node (ref "C11") (pin "1") (pinfunction "1_1") (pintype "passive"))
      (node (ref "C12") (pin "1") (pinfunction "1_1") (pintype "passive"))
      (node (ref "C13") (pin "1") (pinfunction "1_1") (pintype "passive"))
      (node (ref "C14") (pin "1") (pinfunction "1_1") (pintype "passive"))
      (node (ref "C15") (pin "1") (pinfunction "1_1") (pintype "passive"))
      (node (ref "C16") (pin "1") (pinfunction "1_1") (pintype "passive"))
      (node (ref "C17") (pin "1") (pinfunction "1_1") (pintype "passive"))
      (node (ref "C18") (pin "1") (pinfunction "1_1") (pintype "passive"))
      (node (ref "C2") (pin "1") (pinfunction "1_1") (pintype "passive"))
      (node (ref "C3") (pin "1") (pinfunction "1_1") (pintype "passive"))
      (node (ref "C4") (pin "2") (pinfunction "2_2") (pintype "passive"))
      (node (ref "C5") (pin "2") (pinfunction "2_2") (pintype "passive"))
      (node (ref "C6") (pin "2") (pinfunction "2_2") (pintype "passive"))
      (node (ref "C7") (pin "2") (pinfunction "2_2") (pintype "passive"))
      (node (ref "C8") (pin "1") (pinfunction "1_1") (pintype "passive"))
      (node (ref "C9") (pin "1") (pinfunction "1_1") (pintype "passive"))
      (node (ref "D1") (pin "1") (pinfunction "A_1") (pintype "passive"))
      (node (ref "D2") (pin "2") (pinfunction "K_2") (pintype "passive"))
      (node (ref "J1") (pin "4") (pinfunction "VSS_4") (pintype "passive"))
      (node (ref "J1") (pin "5") (pinfunction "SHELL_5") (pintype "passive"))
      (node (ref "J1") (pin "6") (pinfunction "SHELL_6") (pintype "passive"))
      (node (ref "J2") (pin "2") (pinfunction "2_2") (pintype "power_in"))
      (node (ref "J2") (pin "3") (pinfunction "3_3") (pintype "power_in"))
      (node (ref "J3") (pin "2") (pinfunction "2_2") (pintype "power_in"))
      (node (ref "J3") (pin "3") (pinfunction "3_3") (pintype "power_in"))
      (node (ref "P1") (pin "10") (pinfunction "10_10") (pintype "passive"))
      (node (ref "P1") (pin "12") (pinfunction "12_12") (pintype "passive"))
      (node (ref "P1") (pin "14") (pinfunction "14_14") (pintype "passive"))
      (node (ref "P1") (pin "16") (pinfunction "16_16") (pintype "passive"))
      (node (ref "P1") (pin "18") (pinfunction "18_18") (pintype "passive"))
      (node (ref "P1") (pin "20") (pinfunction "20_20") (pintype "passive"))
      (node (ref "P1") (pin "4") (pinfunction "4_4") (pintype "passive"))
      (node (ref "P1") (pin "6") (pinfunction "6_6") (pintype "passive"))
      (node (ref "P1") (pin "8") (pinfunction "8_8") (pintype "passive"))
      (node (ref "P12") (pin "1") (pinfunction "1_1") (pintype "passive"))
      (node (ref "P12") (pin "2") (pinfunction "2_2") (pintype "passive"))
      (node (ref "P12") (pin "3") (pinfunction "3_3") (pintype "passive"))
      (node (ref "P12") (pin "4") (pinfunction "4_4") (pintype "passive"))
      (node (ref "P12") (pin "5") (pinfunction "5_5") (pintype "passive"))
      (node (ref "P13") (pin "2") (pinfunction "2_2") (pintype "passive"))
      (node (ref "P14") (pin "2") (pinfunction "2_2") (pintype "passive"))
      (node (ref "P15") (pin "5") (pinfunction "5_5") (pintype "passive"))
      (node (ref "P16") (pin "5") (pinfunction "5_5") (pintype "passive"))
      (node (ref "P2") (pin "1") (pinfunction "1_1") (pintype "passive"))
      (node (ref "P2") (pin "12") (pinfunction "12_12") (pintype "passive"))
      (node (ref "P4") (pin "4") (pinfunction "4_4") (pintype "passive"))
      (node (ref "P5") (pin "4") (pinfunction "4_4") (pintype "passive"))
      (node (ref "P9") (pin "12") (pinfunction "12_12") (pintype "passive"))
      (node (ref "P9") (pin "3") (pinfunction "3_3") (pintype "passive"))
      (node (ref "R24") (pin "1") (pinfunction "1_1") (pintype "passive"))
      (node (ref "R25") (pin "1") (pinfunction "1_1") (pintype "passive"))
      (node (ref "R4") (pin "2") (pinfunction "2_2") (pintype "passive"))
      (node (ref "R5") (pin "2") (pinfunction "2_2") (pintype "passive"))
      (node (ref "S3") (pin "2") (pinfunction "2_2") (pintype "passive"))
      (node (ref "U1") (pin "1") (pinfunction "GND_1") (pintype "passive"))
      (node (ref "U2") (pin "10") (pinfunction "VSS_5_10") (pintype "passive"))
      (node (ref "U2") (pin "19") (pinfunction "VSSA_19") (pintype "passive"))
      (node (ref "U2") (pin "20") (pinfunction "VREF-_20") (pintype "passive"))
      (node (ref "U2") (pin "27") (pinfunction "VSS_4_27") (pintype "passive"))
      (node (ref "U2") (pin "49") (pinfunction "VSS_1_49") (pintype "passive"))
      (node (ref "U2") (pin "74") (pinfunction "VSS_2_74") (pintype "passive"))
      (node (ref "U2") (pin "99") (pinfunction "VSS_3_99") (pintype "passive"))
      (node (ref "U3") (pin "8") (pinfunction "GND_8") (pintype "power_in"))
      (node (ref "U4") (pin "2") (pinfunction "2_2") (pintype "passive"))
      (node (ref "U4") (pin "4") (pinfunction "4_4") (pintype "passive"))
      (node (ref "U4") (pin "5") (pinfunction "5_5") (pintype "passive"))
      (node (ref "U4") (pin "7") (pinfunction "7_7") (pintype "passive"))
      (node (ref "U5") (pin "1") (pinfunction "GND_1") (pintype "passive"))
    )
    (net (code "81") (name "Net-(D2-A)") (class "Default")
      (node (ref "D2") (pin "1") (pinfunction "A_1") (pintype "passive"))
      (node (ref "R1") (pin "2") (pinfunction "2_2") (pintype "passive"))
    )
    (net (code "82") (name "Net-(D3-A)") (class "Default")
      (node (ref "D3") (pin "1") (pinfunction "A_1") (pintype "passive"))
      (node (ref "U2") (pin "1") (pinfunction "PE2/TRACECK/RSMC_A23_1") (pintype "passive"))
    )
    (net (code "83") (name "Net-(D3-K)") (class "Default")
      (node (ref "D3") (pin "2") (pinfunction "K_2") (pintype "passive"))
      (node (ref "R25") (pin "2") (pinfunction "2_2") (pintype "passive"))
    )
    (net (code "84") (name "Net-(D4-K)") (class "Default")
      (node (ref "D4") (pin "2") (pinfunction "K_2") (pintype "passive"))
      (node (ref "R27") (pin "1") (pinfunction "1_1") (pintype "passive"))
    )
    (net (code "85") (name "Net-(D5-K)") (class "Default")
      (node (ref "D5") (pin "2") (pinfunction "K_2") (pintype "passive"))
      (node (ref "R26") (pin "2") (pinfunction "2_2") (pintype "passive"))
    )
    (net (code "86") (name "Net-(F1-Pad1)") (class "Default")
      (node (ref "F1") (pin "1") (pinfunction "1_1") (pintype "passive"))
      (node (ref "S2") (pin "1") (pinfunction "1_1") (pintype "passive"))
    )
    (net (code "87") (name "Net-(F2-Pad1)") (class "Default")
      (node (ref "F2") (pin "1") (pinfunction "1_1") (pintype "passive"))
      (node (ref "S2") (pin "6") (pinfunction "6_6") (pintype "passive"))
    )
    (net (code "88") (name "Net-(P1-Pad19)") (class "Default")
      (node (ref "P1") (pin "19") (pinfunction "19_19") (pintype "passive"))
      (node (ref "P3") (pin "1") (pinfunction "1_1") (pintype "passive"))
    )
    (net (code "89") (name "Net-(R10-Pad1)") (class "Default")
      (node (ref "R10") (pin "1") (pinfunction "1_1") (pintype "passive"))
      (node (ref "R14") (pin "1") (pinfunction "1_1") (pintype "passive"))
      (node (ref "U4") (pin "8") (pinfunction "8_8") (pintype "passive"))
    )
    (net (code "90") (name "Net-(R11-Pad1)") (class "Default")
      (node (ref "R11") (pin "1") (pinfunction "1_1") (pintype "passive"))
      (node (ref "R18") (pin "1") (pinfunction "1_1") (pintype "passive"))
      (node (ref "U4") (pin "6") (pinfunction "6_6") (pintype "passive"))
    )
    (net (code "91") (name "Net-(R13-Pad2)") (class "Default")
      (node (ref "R13") (pin "2") (pinfunction "2_2") (pintype "passive"))
      (node (ref "U4") (pin "1") (pinfunction "1_1") (pintype "passive"))
    )
    (net (code "92") (name "Net-(R17-Pad2)") (class "Default")
      (node (ref "R17") (pin "2") (pinfunction "2_2") (pintype "passive"))
      (node (ref "U4") (pin "3") (pinfunction "3_3") (pintype "passive"))
    )
    (net (code "93") (name "Net-(S1-A1)") (class "Default")
      (node (ref "R3") (pin "1") (pinfunction "1_1") (pintype "passive"))
      (node (ref "S1") (pin "1") (pinfunction "A1_1") (pintype "passive"))
    )
    (net (code "94") (name "Net-(S1-A2)") (class "Default")
      (node (ref "R2") (pin "1") (pinfunction "1_1") (pintype "passive"))
      (node (ref "S1") (pin "2") (pinfunction "A2_2") (pintype "passive"))
    )
    (net (code "95") (name "Net-(U2-OSC_IN)") (class "Default")
      (node (ref "C7") (pin "1") (pinfunction "1_1") (pintype "passive"))
      (node (ref "U2") (pin "12") (pinfunction "OSC_IN_12") (pintype "passive"))
      (node (ref "Y1") (pin "2") (pinfunction "OSC2_2") (pintype "passive"))
    )
    (net (code "96") (name "Net-(U2-OSC_OUT)") (class "Default")
      (node (ref "C6") (pin "1") (pinfunction "1_1") (pintype "passive"))
      (node (ref "U2") (pin "13") (pinfunction "OSC_OUT_13") (pintype "passive"))
      (node (ref "Y1") (pin "1") (pinfunction "OSC1_1") (pintype "passive"))
    )
    (net (code "97") (name "Net-(U3-QA)") (class "Default")
      (node (ref "R12") (pin "1") (pinfunction "1_1") (pintype "passive"))
      (node (ref "U3") (pin "15") (pinfunction "QA_15") (pintype "tri_state"))
    )
    (net (code "98") (name "Net-(U3-QB)") (class "Default")
      (node (ref "R15") (pin "1") (pinfunction "1_1") (pintype "passive"))
      (node (ref "U3") (pin "1") (pinfunction "QB_1") (pintype "tri_state"))
    )
    (net (code "99") (name "Net-(U3-QC)") (class "Default")
      (node (ref "R16") (pin "1") (pinfunction "1_1") (pintype "passive"))
      (node (ref "U3") (pin "2") (pinfunction "QC_2") (pintype "tri_state"))
    )
    (net (code "100") (name "Net-(U3-QD)") (class "Default")
      (node (ref "R19") (pin "1") (pinfunction "1_1") (pintype "passive"))
      (node (ref "U3") (pin "3") (pinfunction "QD_3") (pintype "tri_state"))
    )
    (net (code "101") (name "Net-(U3-QE)") (class "Default")
      (node (ref "R20") (pin "1") (pinfunction "1_1") (pintype "passive"))
      (node (ref "U3") (pin "4") (pinfunction "QE_4") (pintype "tri_state"))
    )
    (net (code "102") (name "Net-(U3-QF)") (class "Default")
      (node (ref "R21") (pin "1") (pinfunction "1_1") (pintype "passive"))
      (node (ref "U3") (pin "5") (pinfunction "QF_5") (pintype "tri_state"))
    )
    (net (code "103") (name "Net-(U3-QG)") (class "Default")
      (node (ref "R22") (pin "1") (pinfunction "1_1") (pintype "passive"))
      (node (ref "U3") (pin "6") (pinfunction "QG_6") (pintype "tri_state"))
    )
    (net (code "104") (name "Net-(U3-QH)") (class "Default")
      (node (ref "R23") (pin "1") (pinfunction "1_1") (pintype "passive"))
      (node (ref "U3") (pin "7") (pinfunction "QH_7") (pintype "tri_state"))
    )
    (net (code "105") (name "Net-(U5-XI)") (class "Default")
      (node (ref "C12") (pin "2") (pinfunction "2_2") (pintype "passive"))
      (node (ref "U5") (pin "7") (pinfunction "XI_7") (pintype "passive"))
      (node (ref "Y2") (pin "2") (pinfunction "OSC2_2") (pintype "passive"))
    )
    (net (code "106") (name "Net-(U5-XO)") (class "Default")
      (node (ref "C13") (pin "2") (pinfunction "2_2") (pintype "passive"))
      (node (ref "U5") (pin "8") (pinfunction "XO_8") (pintype "passive"))
      (node (ref "Y2") (pin "1") (pinfunction "OSC1_1") (pintype "passive"))
    )
    (net (code "107") (name "unconnected-(P1-Pad11)") (class "Default")
      (node (ref "P1") (pin "11") (pinfunction "11_11") (pintype "passive"))
    )
    (net (code "108") (name "unconnected-(P1-Pad17)") (class "Default")
      (node (ref "P1") (pin "17") (pinfunction "17_17") (pintype "passive"))
    )
    (net (code "109") (name "unconnected-(S2-Pad3)") (class "Default")
      (node (ref "S2") (pin "3") (pinfunction "3_3") (pintype "passive"))
    )
    (net (code "110") (name "unconnected-(S2-Pad4)") (class "Default")
      (node (ref "S2") (pin "4") (pinfunction "4_4") (pintype "passive"))
    )
    (net (code "111") (name "unconnected-(U2-NC-Pad73)") (class "Default")
      (node (ref "U2") (pin "73") (pinfunction "NC_73") (pintype "passive"))
    )
    (net (code "112") (name "unconnected-(U2-PB5{slash}I2C1_SMBA{slash}I2S3_SD{slash}SPI3_MOSI{slash}T3C2{slash}SPI1_MOSI-Pad91)") (class "Default")
      (node (ref "U2") (pin "91") (pinfunction "PB5/I2C1_SMBA/I2S3_SD/SPI3_MOSI/T3C2/SPI1_MOSI_91") (pintype "passive"))
    )
    (net (code "113") (name "unconnected-(U2-PB10{slash}USART3_Tx{slash}I2C2_SCL{slash}T2C3-Pad47)") (class "Default")
      (node (ref "U2") (pin "47") (pinfunction "PB10/USART3_Tx/I2C2_SCL/T2C3_47") (pintype "passive"))
    )
    (net (code "114") (name "unconnected-(U2-PB11{slash}USART3_Rx{slash}I2C2_SDA{slash}T2C4-Pad48)") (class "Default")
      (node (ref "U2") (pin "48") (pinfunction "PB11/USART3_Rx/I2C2_SDA/T2C4_48") (pintype "passive"))
    )
    (net (code "115") (name "unconnected-(U2-PB12{slash}I2S2_WS{slash}T1BKIN{slash}SPI2_NSS{slash}I2C2_SMBA-Pad51)") (class "Default")
      (node (ref "U2") (pin "51") (pinfunction "PB12/I2S2_WS/T1BKIN/SPI2_NSS/I2C2_SMBA_51") (pintype "passive"))
    )
    (net (code "116") (name "unconnected-(U2-PD0{slash}CAN_Rx{slash}FSMC_D2-Pad81)") (class "Default")
      (node (ref "U2") (pin "81") (pinfunction "PD0/CAN_Rx/FSMC_D2_81") (pintype "passive"))
    )
    (net (code "117") (name "unconnected-(U2-PD1{slash}CAN_Tx{slash}FSMC_D3-Pad82)") (class "Default")
      (node (ref "U2") (pin "82") (pinfunction "PD1/CAN_Tx/FSMC_D3_82") (pintype "passive"))
    )
    (net (code "118") (name "unconnected-(U2-PD2{slash}UART5_Rx{slash}T3ETR{slash}SDIO_CMD-Pad83)") (class "Default")
      (node (ref "U2") (pin "83") (pinfunction "PD2/UART5_Rx/T3ETR/SDIO_CMD_83") (pintype "passive"))
    )
    (net (code "119") (name "unconnected-(U2-PD3{slash}FSMC_CLK-Pad84)") (class "Default")
      (node (ref "U2") (pin "84") (pinfunction "PD3/FSMC_CLK_84") (pintype "passive"))
    )
    (net (code "120") (name "unconnected-(U2-PD4{slash}FSMC_NOE-Pad85)") (class "Default")
      (node (ref "U2") (pin "85") (pinfunction "PD4/FSMC_NOE_85") (pintype "passive"))
    )
    (net (code "121") (name "unconnected-(U2-PD5{slash}USART2_Tx{slash}FSMC_NWE-Pad86)") (class "Default")
      (node (ref "U2") (pin "86") (pinfunction "PD5/USART2_Tx/FSMC_NWE_86") (pintype "passive"))
    )
    (net (code "122") (name "unconnected-(U2-PD6{slash}USART2_Rx{slash}FSMC_NWAIT-Pad87)") (class "Default")
      (node (ref "U2") (pin "87") (pinfunction "PD6/USART2_Rx/FSMC_NWAIT_87") (pintype "passive"))
    )
    (net (code "123") (name "unconnected-(U2-PD7{slash}FSMC_NE1{slash}FSMC_NCE2-Pad88)") (class "Default")
      (node (ref "U2") (pin "88") (pinfunction "PD7/FSMC_NE1/FSMC_NCE2_88") (pintype "passive"))
    )
    (net (code "124") (name "unconnected-(U2-PE3{slash}TRACED0{slash}FSMC_A19-Pad2)") (class "Default")
      (node (ref "U2") (pin "2") (pinfunction "PE3/TRACED0/FSMC_A19_2") (pintype "passive"))
    )
    (net (code "125") (name "unconnected-(U2-PE4{slash}TRACED1{slash}FSMC_A20-Pad3)") (class "Default")
      (node (ref "U2") (pin "3") (pinfunction "PE4/TRACED1/FSMC_A20_3") (pintype "passive"))
    )
    (net (code "126") (name "unconnected-(U2-PE5{slash}TRACED2{slash}FSMC_A21-Pad4)") (class "Default")
      (node (ref "U2") (pin "4") (pinfunction "PE5/TRACED2/FSMC_A21_4") (pintype "passive"))
    )
    (net (code "127") (name "unconnected-(U2-PE6{slash}TRACED3{slash}FSMC_A22-Pad5)") (class "Default")
      (node (ref "U2") (pin "5") (pinfunction "PE6/TRACED3/FSMC_A22_5") (pintype "passive"))
    )
    (net (code "128") (name "unconnected-(U2-PE10{slash}FSMC_D7{slash}T1CH2N-Pad41)") (class "Default")
      (node (ref "U2") (pin "41") (pinfunction "PE10/FSMC_D7/T1CH2N_41") (pintype "passive"))
    )
    (net (code "129") (name "unconnected-(U2-PE11{slash}FSMC_D8{slash}T1C2-Pad42)") (class "Default")
      (node (ref "U2") (pin "42") (pinfunction "PE11/FSMC_D8/T1C2_42") (pintype "passive"))
    )
    (net (code "130") (name "unconnected-(U2-PE12{slash}FSMC_D9{slash}T1CH3N-Pad43)") (class "Default")
      (node (ref "U2") (pin "43") (pinfunction "PE12/FSMC_D9/T1CH3N_43") (pintype "passive"))
    )
    (net (code "131") (name "unconnected-(U2-PE13{slash}FSMC_D10{slash}T1C3-Pad44)") (class "Default")
      (node (ref "U2") (pin "44") (pinfunction "PE13/FSMC_D10/T1C3_44") (pintype "passive"))
    )
    (net (code "132") (name "unconnected-(U2-PE14{slash}FSMC_D11{slash}T1C4-Pad45)") (class "Default")
      (node (ref "U2") (pin "45") (pinfunction "PE14/FSMC_D11/T1C4_45") (pintype "passive"))
    )
    (net (code "133") (name "unconnected-(U2-PE15{slash}FSMC_D12{slash}T1BKIN-Pad46)") (class "Default")
      (node (ref "U2") (pin "46") (pinfunction "PE15/FSMC_D12/T1BKIN_46") (pintype "passive"))
    )
    (net (code "134") (name "unconnected-(U3-SDO-Pad9)") (class "Default")
      (node (ref "U3") (pin "9") (pinfunction "SDO_9") (pintype "output"))
    )
    (net (code "135") (name "unconnected-(U5-CTS#-Pad9)") (class "Default")
      (node (ref "U5") (pin "9") (pinfunction "CTS#_9") (pintype "passive"))
    )
    (net (code "136") (name "unconnected-(U5-DCD#-Pad13)") (class "Default")
      (node (ref "U5") (pin "13") (pinfunction "DCD#_13") (pintype "passive"))
    )
    (net (code "137") (name "unconnected-(U5-DSR#-Pad15)") (class "Default")
      (node (ref "U5") (pin "15") (pinfunction "DSR#_15") (pintype "passive"))
    )
    (net (code "138") (name "unconnected-(U5-DTR#-Pad12)") (class "Default")
      (node (ref "U5") (pin "12") (pinfunction "DTR#_12") (pintype "passive"))
    )
    (net (code "139") (name "unconnected-(U5-R232-Pad10)") (class "Default")
      (node (ref "U5") (pin "10") (pinfunction "R232_10") (pintype "passive"))
    )
    (net (code "140") (name "unconnected-(U5-RI#-Pad14)") (class "Default")
      (node (ref "U5") (pin "14") (pinfunction "RI#_14") (pintype "passive"))
    )
    (net (code "141") (name "unconnected-(U5-RTS#-Pad11)") (class "Default")
      (node (ref "U5") (pin "11") (pinfunction "RTS#_11") (pintype "passive"))
    )
  )
)
